# led.net
KiCad netlist of a schematic drawn in EAGLE
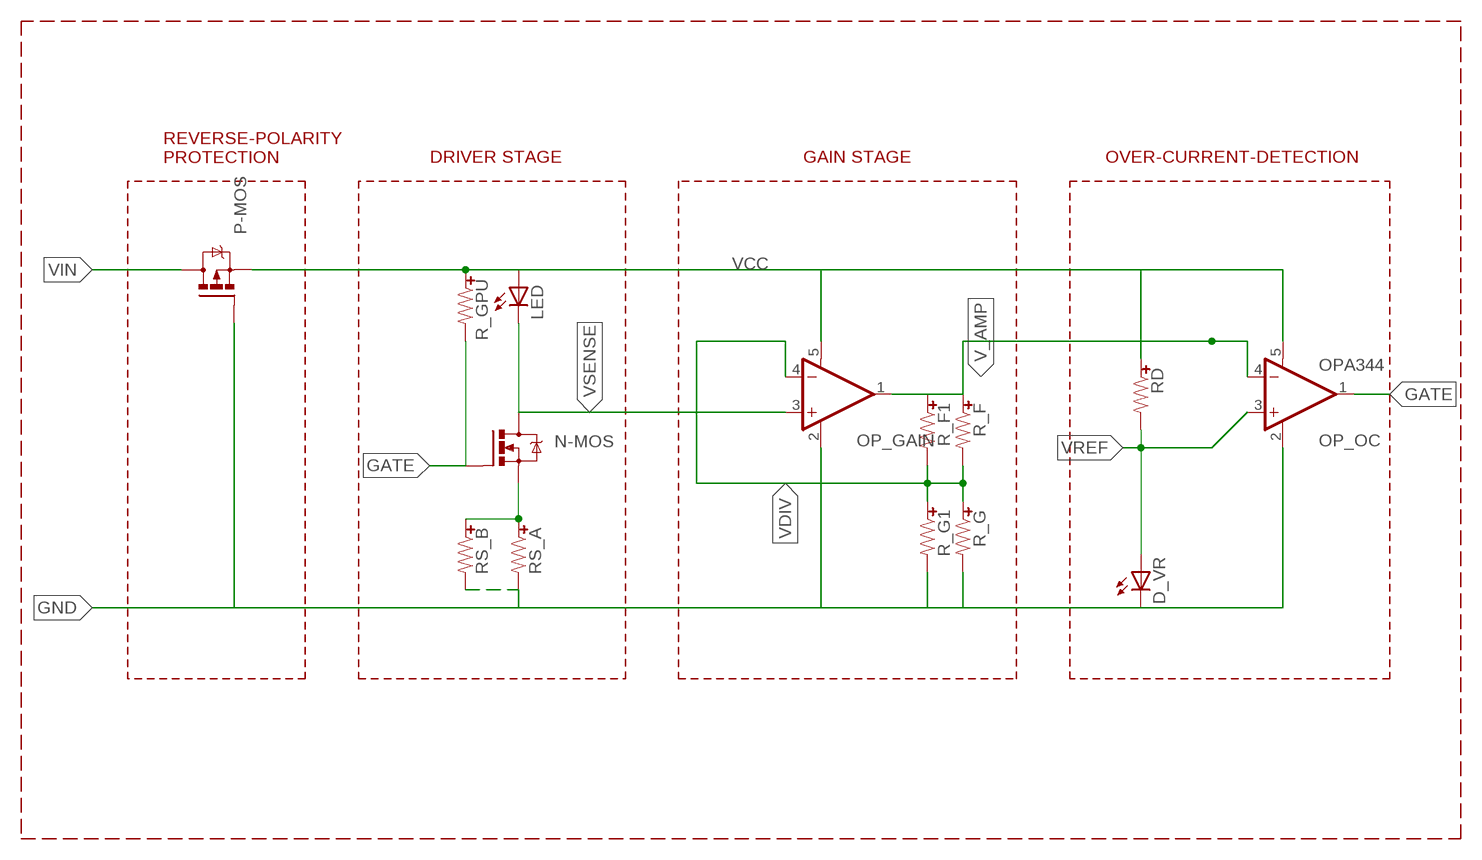
[diagram p0: schematic, sheet 1]

(export (version "E")
  (design (tool "Eeschema 10.0.6"))
  (components
    (comp (ref "D_VR")
      (value "LEDUNIVERSAL")
      (footprint "eagle-import:0402-0603-0805-UNIVERSAL")
      (libsource (lib "eagle-import") (part "LEDUNIVERSAL"))
    )
    (comp (ref "LED")
      (value "LEDUNIVERSAL")
      (footprint "eagle-import:0402-0603-0805-UNIVERSAL")
      (libsource (lib "eagle-import") (part "LEDUNIVERSAL"))
    )
    (comp (ref "N-MOS")
      (value "MOSFET-NCHANNELSMD")
      (footprint "eagle-import:SOT23-3")
      (libsource (lib "eagle-import") (part "MOSFET-NCHANNELSMD"))
    )
    (comp (ref "OP_GAIN")
      (value "OPA344")
      (footprint "eagle-import:SOT23-5")
      (libsource (lib "eagle-import") (part "OPA344"))
    )
    (comp (ref "OP_OC")
      (value "OPA344")
      (footprint "eagle-import:SOT23-5")
      (libsource (lib "eagle-import") (part "OPA344"))
    )
    (comp (ref "P-MOS")
      (value "MOSFET-PCHANNEL")
      (footprint "eagle-import:SOT23-3")
      (libsource (lib "eagle-import") (part "MOSFET-PCHANNEL"))
    )
    (comp (ref "RD")
      (value "RESISTORUNIVERSAL")
      (footprint "eagle-import:0402-0603-0805-UNIVERSAL")
      (libsource (lib "eagle-import") (part "RESISTORUNIVERSAL"))
    )
    (comp (ref "RS_A")
      (value "RESISTORUNIVERSAL")
      (footprint "eagle-import:0402-0603-0805-UNIVERSAL")
      (libsource (lib "eagle-import") (part "RESISTORUNIVERSAL"))
    )
    (comp (ref "RS_B")
      (value "RESISTORUNIVERSAL")
      (footprint "eagle-import:0402-0603-0805-UNIVERSAL")
      (libsource (lib "eagle-import") (part "RESISTORUNIVERSAL"))
    )
    (comp (ref "R_F")
      (value "RESISTORUNIVERSAL")
      (footprint "eagle-import:0402-0603-0805-UNIVERSAL")
      (libsource (lib "eagle-import") (part "RESISTORUNIVERSAL"))
    )
    (comp (ref "R_F1")
      (value "RESISTORUNIVERSAL")
      (footprint "eagle-import:0402-0603-0805-UNIVERSAL")
      (libsource (lib "eagle-import") (part "RESISTORUNIVERSAL"))
    )
    (comp (ref "R_G")
      (value "RESISTORUNIVERSAL")
      (footprint "eagle-import:0402-0603-0805-UNIVERSAL")
      (libsource (lib "eagle-import") (part "RESISTORUNIVERSAL"))
    )
    (comp (ref "R_G1")
      (value "RESISTORUNIVERSAL")
      (footprint "eagle-import:0402-0603-0805-UNIVERSAL")
      (libsource (lib "eagle-import") (part "RESISTORUNIVERSAL"))
    )
    (comp (ref "R_GPU")
      (value "RESISTORUNIVERSAL")
      (footprint "eagle-import:0402-0603-0805-UNIVERSAL")
      (libsource (lib "eagle-import") (part "RESISTORUNIVERSAL"))
    )
  )
  (nets
    (net (code "1") (name "/VCC") (class "Default")
      (node (ref "LED") (pin "+") (pinfunction "A_+") (pintype "passive"))
      (node (ref "OP_GAIN") (pin "5") (pinfunction "V+_5") (pintype "power_in"))
      (node (ref "OP_OC") (pin "5") (pinfunction "V+_5") (pintype "power_in"))
      (node (ref "P-MOS") (pin "2") (pinfunction "S_2") (pintype "passive"))
      (node (ref "RD") (pin "+") (pinfunction "1_+") (pintype "passive"))
      (node (ref "R_GPU") (pin "+") (pinfunction "1_+") (pintype "passive"))
    )
    (net (code "2") (name "GATE") (class "Default")
      (node (ref "N-MOS") (pin "1") (pinfunction "G_1") (pintype "passive"))
      (node (ref "OP_OC") (pin "1") (pinfunction "OUT_1") (pintype "output"))
      (node (ref "R_GPU") (pin "-") (pinfunction "2_-") (pintype "passive"))
    )
    (net (code "3") (name "GND") (class "Default")
      (node (ref "D_VR") (pin "-") (pinfunction "C_-") (pintype "passive"))
      (node (ref "OP_GAIN") (pin "2") (pinfunction "V-_2") (pintype "power_in"))
      (node (ref "OP_OC") (pin "2") (pinfunction "V-_2") (pintype "power_in"))
      (node (ref "P-MOS") (pin "1") (pinfunction "G_1") (pintype "passive"))
      (node (ref "RS_A") (pin "-") (pinfunction "2_-") (pintype "passive"))
      (node (ref "RS_B") (pin "-") (pinfunction "2_-") (pintype "passive"))
      (node (ref "R_G") (pin "-") (pinfunction "2_-") (pintype "passive"))
      (node (ref "R_G1") (pin "-") (pinfunction "2_-") (pintype "passive"))
    )
    (net (code "4") (name "Net-(N-MOS-S)") (class "Default")
      (node (ref "N-MOS") (pin "2") (pinfunction "S_2") (pintype "passive"))
      (node (ref "RS_A") (pin "+") (pinfunction "1_+") (pintype "passive"))
      (node (ref "RS_B") (pin "+") (pinfunction "1_+") (pintype "passive"))
    )
    (net (code "5") (name "VDIV") (class "Default")
      (node (ref "OP_GAIN") (pin "4") (pinfunction "-IN_4") (pintype "input"))
      (node (ref "R_F") (pin "-") (pinfunction "2_-") (pintype "passive"))
      (node (ref "R_F1") (pin "-") (pinfunction "2_-") (pintype "passive"))
      (node (ref "R_G") (pin "+") (pinfunction "1_+") (pintype "passive"))
      (node (ref "R_G1") (pin "+") (pinfunction "1_+") (pintype "passive"))
    )
    (net (code "6") (name "VIN") (class "Default")
      (node (ref "P-MOS") (pin "3") (pinfunction "D_3") (pintype "passive"))
    )
    (net (code "7") (name "VREF") (class "Default")
      (node (ref "D_VR") (pin "+") (pinfunction "A_+") (pintype "passive"))
      (node (ref "OP_OC") (pin "3") (pinfunction "+IN_3") (pintype "input"))
      (node (ref "RD") (pin "-") (pinfunction "2_-") (pintype "passive"))
    )
    (net (code "8") (name "VSENSE") (class "Default")
      (node (ref "LED") (pin "-") (pinfunction "C_-") (pintype "passive"))
      (node (ref "N-MOS") (pin "3") (pinfunction "D_3") (pintype "passive"))
      (node (ref "OP_GAIN") (pin "3") (pinfunction "+IN_3") (pintype "input"))
    )
    (net (code "9") (name "V_AMP") (class "Default")
      (node (ref "OP_GAIN") (pin "1") (pinfunction "OUT_1") (pintype "output"))
      (node (ref "OP_OC") (pin "4") (pinfunction "-IN_4") (pintype "input"))
      (node (ref "R_F") (pin "+") (pinfunction "1_+") (pintype "passive"))
      (node (ref "R_F1") (pin "+") (pinfunction "1_+") (pintype "passive"))
    )
  )
)
